# circle_9axis.net
KiCad netlist of a schematic drawn in EAGLE
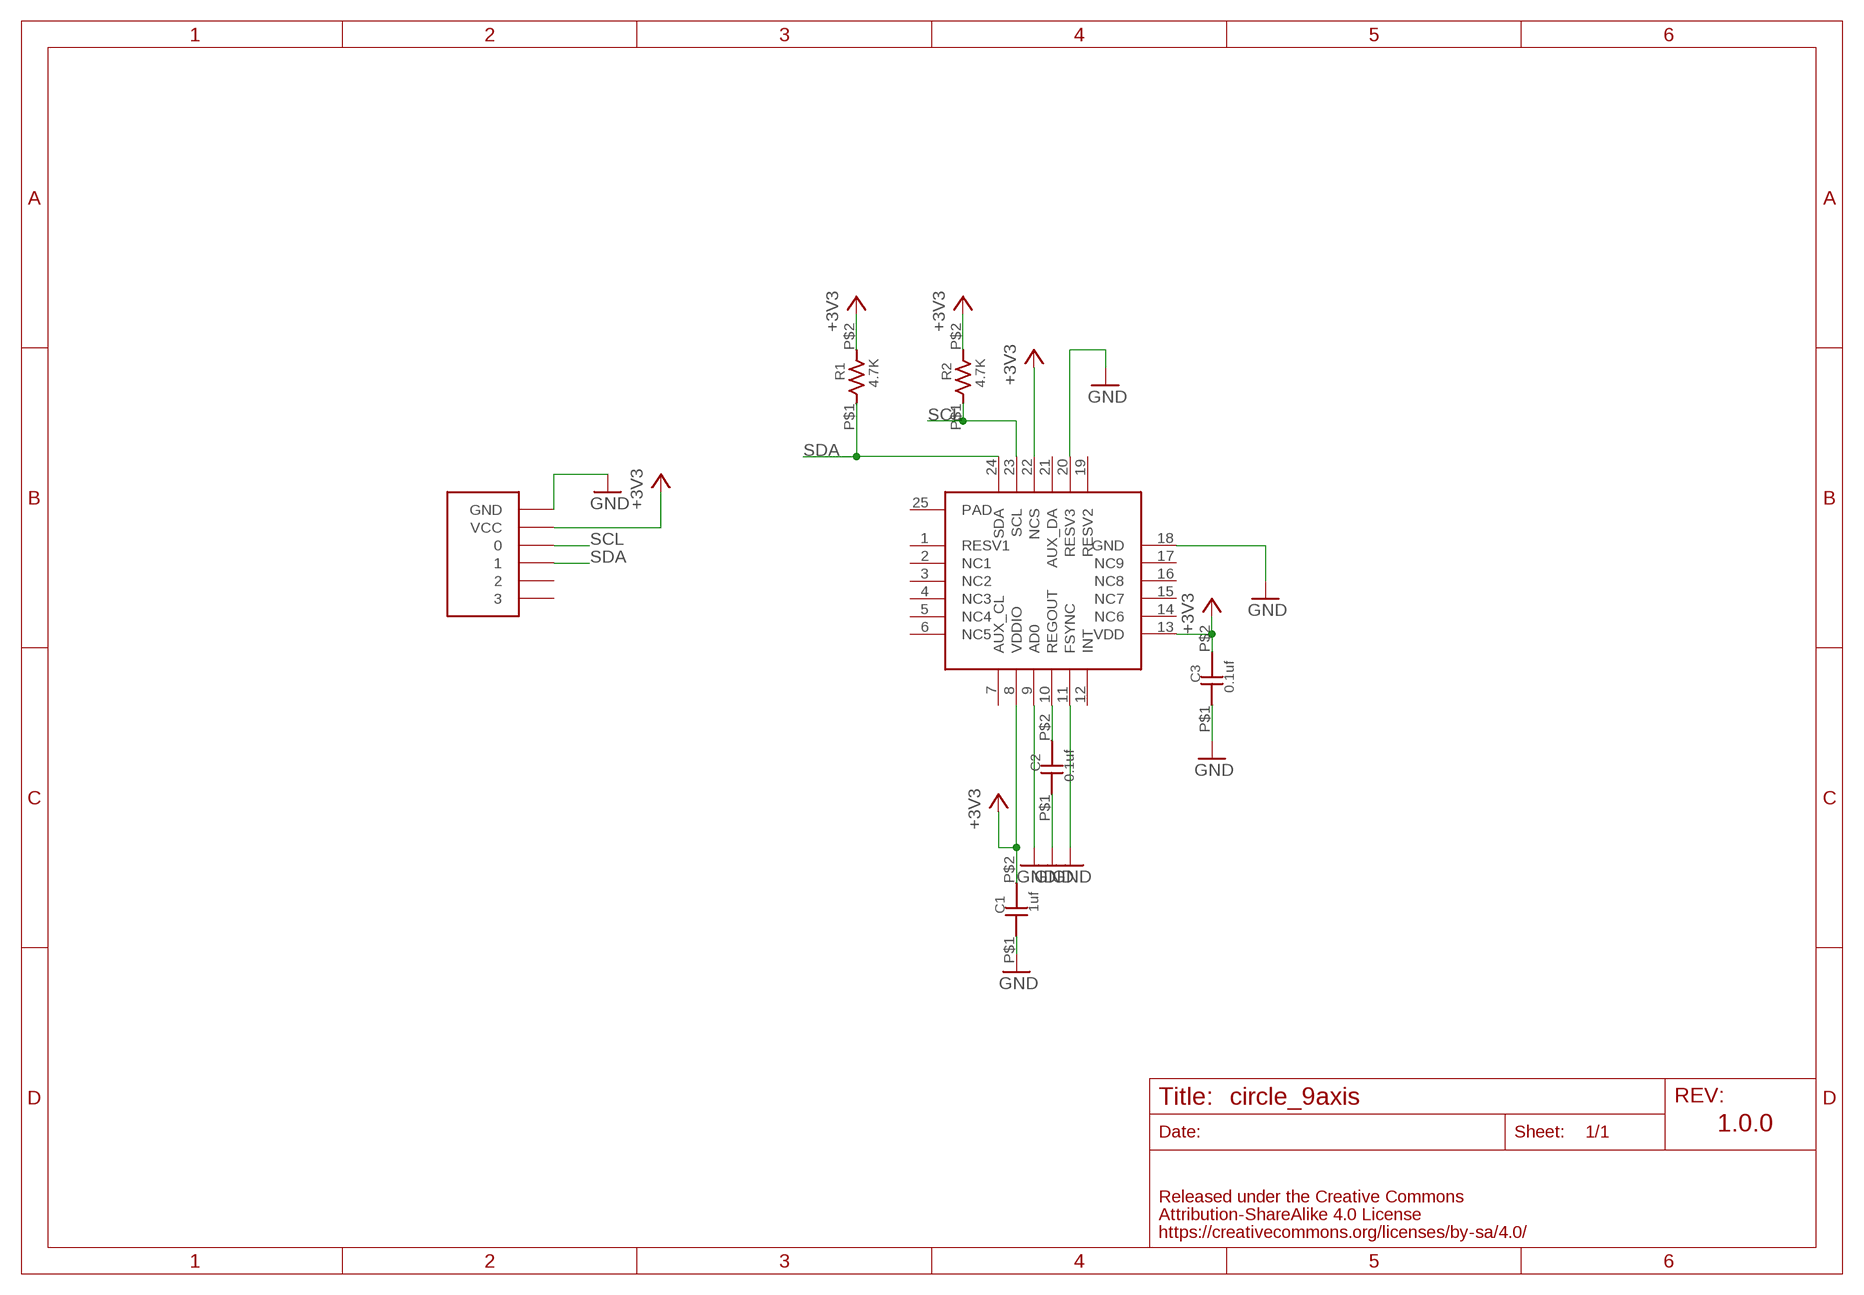
[diagram p0: schematic, sheet 1]

(export (version "E")
  (design (tool "Eeschema 10.0.6"))
  (components
    (comp (ref "C1")
      (value "1uf")
      (footprint "eagle-import:0402")
      (libsource (lib "eagle-import") (part "0402"))
    )
    (comp (ref "C2")
      (value "0.1uf")
      (footprint "eagle-import:0402")
      (libsource (lib "eagle-import") (part "0402"))
    )
    (comp (ref "C3")
      (value "0.1uf")
      (footprint "eagle-import:0402")
      (libsource (lib "eagle-import") (part "0402"))
    )
    (comp (ref "R1")
      (value "4.7K")
      (footprint "eagle-import:0402")
      (libsource (lib "eagle-import") (part "FaBo-Resistors_0402"))
    )
    (comp (ref "R2")
      (value "4.7K")
      (footprint "eagle-import:0402")
      (libsource (lib "eagle-import") (part "FaBo-Resistors_0402"))
    )
    (comp (ref "U$1")
      (value "INVENSENSE-MPU9250")
      (footprint "eagle-import:LGA-24")
      (libsource (lib "eagle-import") (part "INVENSENSE-MPU9250"))
    )
    (comp (ref "U$4")
      (value "FABO-NANO")
      (footprint "eagle-import:FABO-NANO")
      (libsource (lib "eagle-import") (part "FABO-NANO"))
    )
  )
  (nets
    (net (code "1") (name "+3V3") (class "Default")
      (node (ref "C1") (pin "P$2") (pinfunction "2_P$2") (pintype "passive"))
      (node (ref "C3") (pin "P$2") (pinfunction "2_P$2") (pintype "passive"))
      (node (ref "R1") (pin "P$2") (pinfunction "2_P$2") (pintype "passive"))
      (node (ref "R2") (pin "P$2") (pinfunction "2_P$2") (pintype "passive"))
      (node (ref "U$1") (pin "13") (pinfunction "VDD_13") (pintype "bidirectional"))
      (node (ref "U$1") (pin "22") (pinfunction "NCS_22") (pintype "bidirectional"))
      (node (ref "U$1") (pin "8") (pinfunction "VDDIO_8") (pintype "bidirectional"))
      (node (ref "U$4") (pin "VCC") (pinfunction "VCC_VCC") (pintype "bidirectional"))
    )
    (net (code "2") (name "/SCL") (class "Default")
      (node (ref "R2") (pin "P$1") (pinfunction "1_P$1") (pintype "passive"))
      (node (ref "U$1") (pin "23") (pinfunction "SCL_23") (pintype "bidirectional"))
      (node (ref "U$4") (pin "0") (pinfunction "0_0") (pintype "bidirectional"))
    )
    (net (code "3") (name "/SDA") (class "Default")
      (node (ref "R1") (pin "P$1") (pinfunction "1_P$1") (pintype "passive"))
      (node (ref "U$1") (pin "24") (pinfunction "SDA_24") (pintype "bidirectional"))
      (node (ref "U$4") (pin "1") (pinfunction "1_1") (pintype "bidirectional"))
    )
    (net (code "4") (name "GND") (class "Default")
      (node (ref "C1") (pin "P$1") (pinfunction "1_P$1") (pintype "passive"))
      (node (ref "C2") (pin "P$1") (pinfunction "1_P$1") (pintype "passive"))
      (node (ref "C3") (pin "P$1") (pinfunction "1_P$1") (pintype "passive"))
      (node (ref "U$1") (pin "11") (pinfunction "FSYNC_11") (pintype "bidirectional"))
      (node (ref "U$1") (pin "18") (pinfunction "GND_18") (pintype "bidirectional"))
      (node (ref "U$1") (pin "20") (pinfunction "RESV3_20") (pintype "bidirectional"))
      (node (ref "U$1") (pin "9") (pinfunction "AD0_9") (pintype "bidirectional"))
      (node (ref "U$4") (pin "GND") (pinfunction "GND_GND") (pintype "bidirectional"))
    )
    (net (code "5") (name "Net-(C2-2)") (class "Default")
      (node (ref "C2") (pin "P$2") (pinfunction "2_P$2") (pintype "passive"))
      (node (ref "U$1") (pin "10") (pinfunction "REGOUT_10") (pintype "bidirectional"))
    )
    (net (code "6") (name "unconnected-(U$1-AUX_CL-Pad7)") (class "Default")
      (node (ref "U$1") (pin "7") (pinfunction "AUX_CL_7") (pintype "bidirectional"))
    )
    (net (code "7") (name "unconnected-(U$1-AUX_DA-Pad21)") (class "Default")
      (node (ref "U$1") (pin "21") (pinfunction "AUX_DA_21") (pintype "bidirectional"))
    )
    (net (code "8") (name "unconnected-(U$1-INT-Pad12)") (class "Default")
      (node (ref "U$1") (pin "12") (pinfunction "INT_12") (pintype "bidirectional"))
    )
    (net (code "9") (name "unconnected-(U$1-NC1-Pad2)") (class "Default")
      (node (ref "U$1") (pin "2") (pinfunction "NC1_2") (pintype "bidirectional"))
    )
    (net (code "10") (name "unconnected-(U$1-NC2-Pad3)") (class "Default")
      (node (ref "U$1") (pin "3") (pinfunction "NC2_3") (pintype "bidirectional"))
    )
    (net (code "11") (name "unconnected-(U$1-NC3-Pad4)") (class "Default")
      (node (ref "U$1") (pin "4") (pinfunction "NC3_4") (pintype "bidirectional"))
    )
    (net (code "12") (name "unconnected-(U$1-NC4-Pad5)") (class "Default")
      (node (ref "U$1") (pin "5") (pinfunction "NC4_5") (pintype "bidirectional"))
    )
    (net (code "13") (name "unconnected-(U$1-NC5-Pad6)") (class "Default")
      (node (ref "U$1") (pin "6") (pinfunction "NC5_6") (pintype "bidirectional"))
    )
    (net (code "14") (name "unconnected-(U$1-NC6-Pad14)") (class "Default")
      (node (ref "U$1") (pin "14") (pinfunction "NC6_14") (pintype "bidirectional"))
    )
    (net (code "15") (name "unconnected-(U$1-NC7-Pad15)") (class "Default")
      (node (ref "U$1") (pin "15") (pinfunction "NC7_15") (pintype "bidirectional"))
    )
    (net (code "16") (name "unconnected-(U$1-NC8-Pad16)") (class "Default")
      (node (ref "U$1") (pin "16") (pinfunction "NC8_16") (pintype "bidirectional"))
    )
    (net (code "17") (name "unconnected-(U$1-NC9-Pad17)") (class "Default")
      (node (ref "U$1") (pin "17") (pinfunction "NC9_17") (pintype "bidirectional"))
    )
    (net (code "18") (name "unconnected-(U$1-PAD-Pad25)") (class "Default")
      (node (ref "U$1") (pin "25") (pinfunction "PAD_25") (pintype "bidirectional"))
    )
    (net (code "19") (name "unconnected-(U$1-RESV1-Pad1)") (class "Default")
      (node (ref "U$1") (pin "1") (pinfunction "RESV1_1") (pintype "bidirectional"))
    )
    (net (code "20") (name "unconnected-(U$1-RESV2-Pad19)") (class "Default")
      (node (ref "U$1") (pin "19") (pinfunction "RESV2_19") (pintype "bidirectional"))
    )
    (net (code "21") (name "unconnected-(U$4-Pad2)") (class "Default")
      (node (ref "U$4") (pin "2") (pinfunction "2_2") (pintype "bidirectional"))
    )
    (net (code "22") (name "unconnected-(U$4-Pad3)") (class "Default")
      (node (ref "U$4") (pin "3") (pinfunction "3_3") (pintype "bidirectional"))
    )
  )
)
